# CSC.net
KiCad netlist of a schematic drawn in EAGLE
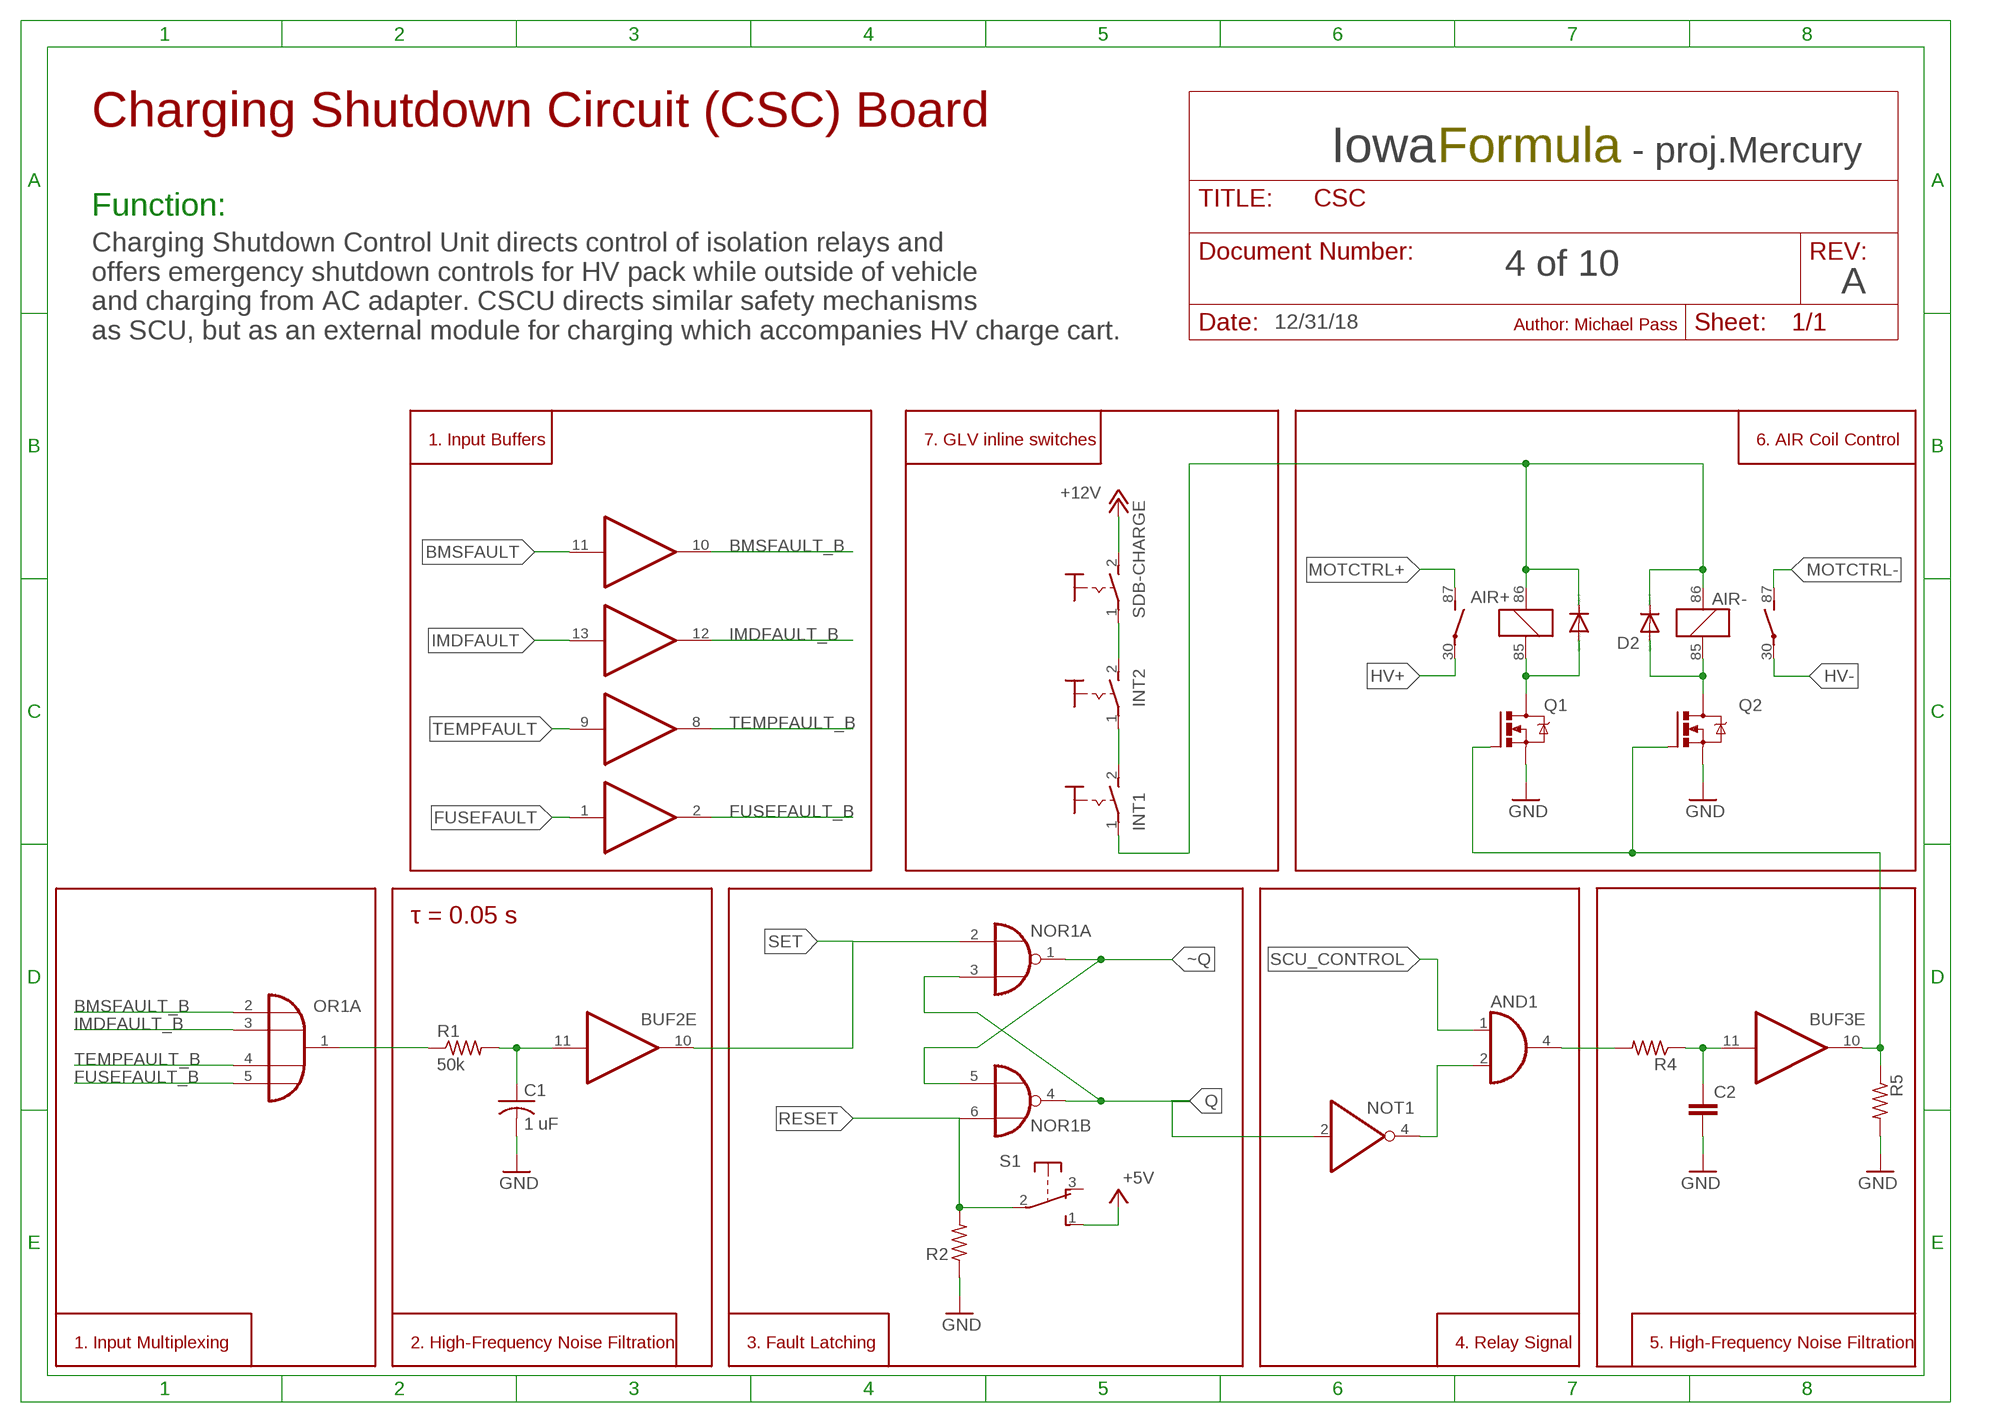
[diagram p0: schematic, sheet 1]

(export (version "E")
  (design (tool "Eeschema 10.0.6"))
  (components
    (comp (ref "AIR+")
      (value "CB1A-P-12V")
      (footprint "eagle-import:CB1")
      (fields (field (name "MF") "AROMAT/ MATSUSHITA"))
      (libsource (lib "eagle-import") (part "CB1A-P-12V"))
    )
    (comp (ref "AIR-")
      (value "CB1A-P-12V")
      (footprint "eagle-import:CB1")
      (fields (field (name "MF") "AROMAT/ MATSUSHITA"))
      (libsource (lib "eagle-import") (part "CB1A-P-12V"))
    )
    (comp (ref "AND1")
      (value "74AHCT1G08DCK")
      (footprint "eagle-import:SC70-5")
      (libsource (lib "eagle-import") (part "741G08DCKAHCT"))
    )
    (comp (ref "BUF1")
      (value "7407D")
      (footprint "eagle-import:SO14")
      (libsource (lib "eagle-import") (part "7407D"))
    )
    (comp (ref "BUF2")
      (value "7407D")
      (footprint "eagle-import:SO14")
      (libsource (lib "eagle-import") (part "7407D"))
    )
    (comp (ref "BUF3")
      (value "7407D")
      (footprint "eagle-import:SO14")
      (libsource (lib "eagle-import") (part "7407D"))
    )
    (comp (ref "C1")
      (value "1 uF")
      (footprint "eagle-import:C0805")
      (libsource (lib "eagle-import") (part "C-USC0805"))
    )
    (comp (ref "C2")
      (value "C-EUC0805")
      (footprint "eagle-import:C0805")
      (libsource (lib "eagle-import") (part "C-EUC0805"))
    )
    (comp (ref "D1")
      (value "1N4933")
      (footprint "eagle-import:DO41-10")
      (libsource (lib "eagle-import") (part "1N4933"))
    )
    (comp (ref "D2")
      (value "1N4933")
      (footprint "eagle-import:DO41-10")
      (libsource (lib "eagle-import") (part "1N4933"))
    )
    (comp (ref "INT1")
      (value "MS243")
      (footprint "eagle-import:MS243")
      (libsource (lib "eagle-import") (part "MS243"))
    )
    (comp (ref "INT2")
      (value "MS243")
      (footprint "eagle-import:MS243")
      (libsource (lib "eagle-import") (part "MS243"))
    )
    (comp (ref "NOR1")
      (value "74LS33D")
      (footprint "eagle-import:SO14")
      (libsource (lib "eagle-import") (part "7433DLS"))
    )
    (comp (ref "NOT1")
      (value "74LVC1G06DCK")
      (footprint "eagle-import:SC70-5")
      (libsource (lib "eagle-import") (part "741G06DCKLVC"))
    )
    (comp (ref "OR1")
      (value "4072D")
      (footprint "eagle-import:SO14")
      (libsource (lib "eagle-import") (part "4072D"))
    )
    (comp (ref "Q1")
      (value "IRLZ44Z")
      (footprint "eagle-import:TO220BH")
      (libsource (lib "eagle-import") (part "IRLZ44Z"))
    )
    (comp (ref "Q2")
      (value "IRLZ44Z")
      (footprint "eagle-import:TO220BH")
      (libsource (lib "eagle-import") (part "IRLZ44Z"))
    )
    (comp (ref "R1")
      (value "50k")
      (footprint "eagle-import:R0805")
      (libsource (lib "eagle-import") (part "R-US_R0805"))
    )
    (comp (ref "R2")
      (value "R-US_R0805")
      (footprint "eagle-import:R0805")
      (libsource (lib "eagle-import") (part "R-US_R0805"))
    )
    (comp (ref "R4")
      (value "R-US_R0805")
      (footprint "eagle-import:R0805")
      (libsource (lib "eagle-import") (part "R-US_R0805"))
    )
    (comp (ref "R5")
      (value "R-US_R0805")
      (footprint "eagle-import:R0805")
      (libsource (lib "eagle-import") (part "R-US_R0805"))
    )
    (comp (ref "S1")
      (value "9077-1")
      (footprint "eagle-import:9077-1")
      (libsource (lib "eagle-import") (part "9077-1"))
    )
    (comp (ref "SDB-CHARGE")
      (value "MS243")
      (footprint "eagle-import:MS243")
      (libsource (lib "eagle-import") (part "MS243"))
    )
  )
  (nets
    (net (code "1") (name "+5V") (class "Default")
      (node (ref "S1") (pin "1") (pinfunction "S_1") (pintype "passive"))
    )
    (net (code "2") (name "+12V") (class "Default")
      (node (ref "SDB-CHARGE") (pin "2") (pinfunction "S_2") (pintype "passive"))
    )
    (net (code "3") (name "/BMSFAULT_B") (class "Default")
      (node (ref "BUF1") (pin "10") (pinfunction "O_10") (pintype "open_collector"))
      (node (ref "OR1") (pin "2") (pinfunction "I0_2") (pintype "input"))
    )
    (net (code "4") (name "/FUSEFAULT_B") (class "Default")
      (node (ref "BUF2") (pin "2") (pinfunction "O_2") (pintype "open_collector"))
      (node (ref "OR1") (pin "5") (pinfunction "I3_5") (pintype "input"))
    )
    (net (code "5") (name "/IMDFAULT_B") (class "Default")
      (node (ref "BUF1") (pin "12") (pinfunction "O_12") (pintype "open_collector"))
      (node (ref "OR1") (pin "3") (pinfunction "I1_3") (pintype "input"))
    )
    (net (code "6") (name "/TEMPFAULT_B") (class "Default")
      (node (ref "BUF1") (pin "8") (pinfunction "O_8") (pintype "open_collector"))
      (node (ref "OR1") (pin "4") (pinfunction "I2_4") (pintype "input"))
    )
    (net (code "7") (name "/~{Q}") (class "Default")
      (node (ref "NOR1") (pin "1") (pinfunction "O_1") (pintype "output"))
      (node (ref "NOR1") (pin "5") (pinfunction "I0_5") (pintype "input"))
    )
    (net (code "8") (name "BMSFAULT") (class "Default")
      (node (ref "BUF1") (pin "11") (pinfunction "I_11") (pintype "input"))
    )
    (net (code "9") (name "FUSEFAULT") (class "Default")
      (node (ref "BUF2") (pin "1") (pinfunction "I_1") (pintype "input"))
    )
    (net (code "10") (name "GND") (class "Default")
      (node (ref "C1") (pin "2") (pinfunction "2_2") (pintype "passive"))
      (node (ref "C2") (pin "2") (pinfunction "2_2") (pintype "passive"))
      (node (ref "Q1") (pin "S") (pinfunction "S_S") (pintype "passive"))
      (node (ref "Q2") (pin "S") (pinfunction "S_S") (pintype "passive"))
      (node (ref "R2") (pin "1") (pinfunction "1_1") (pintype "passive"))
      (node (ref "R5") (pin "2") (pinfunction "2_2") (pintype "passive"))
    )
    (net (code "11") (name "HV+") (class "Default")
      (node (ref "AIR+") (pin "30") (pinfunction "P_30") (pintype "passive"))
    )
    (net (code "12") (name "HV-") (class "Default")
      (node (ref "AIR-") (pin "30") (pinfunction "P_30") (pintype "passive"))
    )
    (net (code "13") (name "IMDFAULT") (class "Default")
      (node (ref "BUF1") (pin "13") (pinfunction "I_13") (pintype "input"))
    )
    (net (code "14") (name "MOTCTRL+") (class "Default")
      (node (ref "AIR+") (pin "87") (pinfunction "S_87") (pintype "passive"))
    )
    (net (code "15") (name "MOTCTRL-") (class "Default")
      (node (ref "AIR-") (pin "87") (pinfunction "S_87") (pintype "passive"))
    )
    (net (code "16") (name "Net-(AIR+A-1)") (class "Default")
      (node (ref "AIR+") (pin "86") (pinfunction "1_86") (pintype "passive"))
      (node (ref "AIR-") (pin "86") (pinfunction "1_86") (pintype "passive"))
      (node (ref "D1") (pin "C") (pinfunction "C_C") (pintype "passive"))
      (node (ref "D2") (pin "C") (pinfunction "C_C") (pintype "passive"))
      (node (ref "INT1") (pin "1") (pinfunction "P_1") (pintype "passive"))
    )
    (net (code "17") (name "Net-(AIR+A-2)") (class "Default")
      (node (ref "AIR+") (pin "85") (pinfunction "2_85") (pintype "passive"))
      (node (ref "D1") (pin "A") (pinfunction "A_A") (pintype "passive"))
      (node (ref "Q1") (pin "D") (pinfunction "D_D") (pintype "passive"))
    )
    (net (code "18") (name "Net-(AIR-A-2)") (class "Default")
      (node (ref "AIR-") (pin "85") (pinfunction "2_85") (pintype "passive"))
      (node (ref "D2") (pin "A") (pinfunction "A_A") (pintype "passive"))
      (node (ref "Q2") (pin "D") (pinfunction "D_D") (pintype "passive"))
    )
    (net (code "19") (name "Net-(AND1A-I1)") (class "Default")
      (node (ref "AND1") (pin "2") (pinfunction "I1_2") (pintype "input"))
      (node (ref "NOT1") (pin "4") (pinfunction "O_4") (pintype "open_collector"))
    )
    (net (code "20") (name "Net-(AND1A-O)") (class "Default")
      (node (ref "AND1") (pin "4") (pinfunction "O_4") (pintype "output"))
      (node (ref "R4") (pin "2") (pinfunction "2_2") (pintype "passive"))
    )
    (net (code "21") (name "Net-(BUF2E-I)") (class "Default")
      (node (ref "BUF2") (pin "11") (pinfunction "I_11") (pintype "input"))
      (node (ref "C1") (pin "1") (pinfunction "1_1") (pintype "passive"))
      (node (ref "R1") (pin "2") (pinfunction "2_2") (pintype "passive"))
    )
    (net (code "22") (name "Net-(BUF3E-I)") (class "Default")
      (node (ref "BUF3") (pin "11") (pinfunction "I_11") (pintype "input"))
      (node (ref "C2") (pin "1") (pinfunction "1_1") (pintype "passive"))
      (node (ref "R4") (pin "1") (pinfunction "1_1") (pintype "passive"))
    )
    (net (code "23") (name "Net-(BUF3E-O)") (class "Default")
      (node (ref "BUF3") (pin "10") (pinfunction "O_10") (pintype "open_collector"))
      (node (ref "Q1") (pin "G") (pinfunction "G_G") (pintype "passive"))
      (node (ref "Q2") (pin "G") (pinfunction "G_G") (pintype "passive"))
      (node (ref "R5") (pin "1") (pinfunction "1_1") (pintype "passive"))
    )
    (net (code "24") (name "Net-(INT1-S)") (class "Default")
      (node (ref "INT1") (pin "2") (pinfunction "S_2") (pintype "passive"))
      (node (ref "INT2") (pin "1") (pinfunction "P_1") (pintype "passive"))
    )
    (net (code "25") (name "Net-(INT2-S)") (class "Default")
      (node (ref "INT2") (pin "2") (pinfunction "S_2") (pintype "passive"))
      (node (ref "SDB-CHARGE") (pin "1") (pinfunction "P_1") (pintype "passive"))
    )
    (net (code "26") (name "Net-(OR1A-O)") (class "Default")
      (node (ref "OR1") (pin "1") (pinfunction "O_1") (pintype "output"))
      (node (ref "R1") (pin "1") (pinfunction "1_1") (pintype "passive"))
    )
    (net (code "27") (name "Q") (class "Default")
      (node (ref "NOR1") (pin "3") (pinfunction "I1_3") (pintype "input"))
      (node (ref "NOR1") (pin "4") (pinfunction "O_4") (pintype "output"))
      (node (ref "NOT1") (pin "2") (pinfunction "I_2") (pintype "input"))
    )
    (net (code "28") (name "RESET") (class "Default")
      (node (ref "NOR1") (pin "6") (pinfunction "I1_6") (pintype "input"))
      (node (ref "R2") (pin "2") (pinfunction "2_2") (pintype "passive"))
      (node (ref "S1") (pin "2") (pinfunction "P_2") (pintype "passive"))
    )
    (net (code "29") (name "SCU_CONTROL") (class "Default")
      (node (ref "AND1") (pin "1") (pinfunction "I0_1") (pintype "input"))
    )
    (net (code "30") (name "SET") (class "Default")
      (node (ref "BUF2") (pin "10") (pinfunction "O_10") (pintype "open_collector"))
      (node (ref "NOR1") (pin "2") (pinfunction "I0_2") (pintype "input"))
    )
    (net (code "31") (name "TEMPFAULT") (class "Default")
      (node (ref "BUF1") (pin "9") (pinfunction "I_9") (pintype "input"))
    )
    (net (code "32") (name "unconnected-(S1-O-Pad3)") (class "Default")
      (node (ref "S1") (pin "3") (pinfunction "O_3") (pintype "passive"))
    )
  )
)
